# ft2232hq.net
KiCad netlist of a schematic drawn in Altium Designer
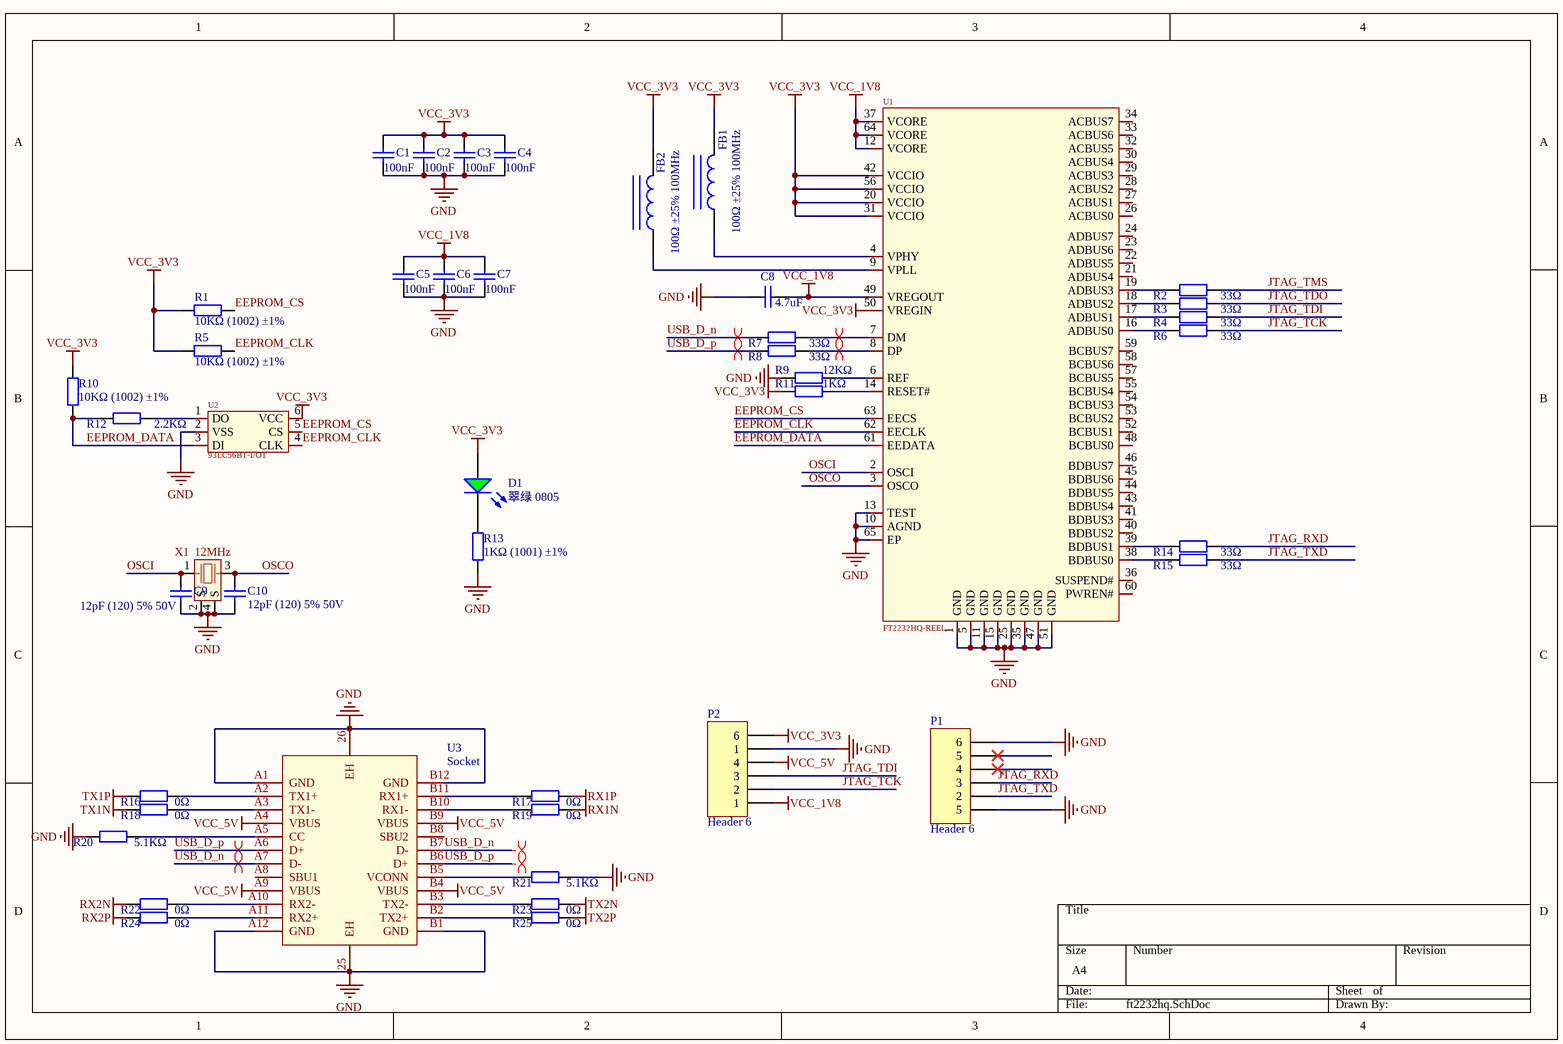
[diagram p0: ft2232hq.SchDoc]

(export (version "E")
  (design (tool "Eeschema 10.0.6"))
  (components
    (comp (ref "C1")
      (value "100nF")
      (footprint "0805_C")
      (description "贴片电容")
      (libsource (lib "Miscellaneous Devices LC") (part "0805 100nF(104) 10% 50V"))
    )
    (comp (ref "C2")
      (value "100nF")
      (footprint "0805_C")
      (description "贴片电容")
      (libsource (lib "Miscellaneous Devices LC") (part "0805 100nF(104) 10% 50V"))
    )
    (comp (ref "C3")
      (value "100nF")
      (footprint "0805_C")
      (description "贴片电容")
      (libsource (lib "Miscellaneous Devices LC") (part "0805 100nF(104) 10% 50V"))
    )
    (comp (ref "C4")
      (value "100nF")
      (footprint "0805_C")
      (description "贴片电容")
      (libsource (lib "Miscellaneous Devices LC") (part "0805 100nF(104) 10% 50V"))
    )
    (comp (ref "C5")
      (value "100nF")
      (footprint "0805_C")
      (description "贴片电容")
      (libsource (lib "Miscellaneous Devices LC") (part "0805 100nF(104) 10% 50V"))
    )
    (comp (ref "C6")
      (value "100nF")
      (footprint "0805_C")
      (description "贴片电容")
      (libsource (lib "Miscellaneous Devices LC") (part "0805 100nF(104) 10% 50V"))
    )
    (comp (ref "C7")
      (value "100nF")
      (footprint "0805_C")
      (description "贴片电容")
      (libsource (lib "Miscellaneous Devices LC") (part "0805 100nF(104) 10% 50V"))
    )
    (comp (ref "C8")
      (value "4.7uF")
      (footprint "0805_C")
      (description "贴片电容")
      (libsource (lib "Miscellaneous Devices LC") (part "0805 4.7uF (475) 10% 25V"))
    )
    (comp (ref "C9")
      (value "12pF (120) 5% 50V")
      (footprint "0805_C")
      (description "贴片电容")
      (libsource (lib "Miscellaneous Devices LC") (part "0805 12pF (120) 5% 50V"))
    )
    (comp (ref "C10")
      (value "12pF (120) 5% 50V")
      (footprint "0805_C")
      (description "贴片电容")
      (libsource (lib "Miscellaneous Devices LC") (part "0805 12pF (120) 5% 50V"))
    )
    (comp (ref "D1")
      (value "翠绿 0805")
      (footprint "0805_LED_S1")
      (description "发光二极管")
      (libsource (lib "Miscellaneous Devices LC") (part "0805 翠绿"))
    )
    (comp (ref "FB1")
      (value "100Ω ±25% 100MHz")
      (footprint "0805_L")
      (description "贴片磁珠")
      (libsource (lib "Miscellaneous Devices LC") (part "0805 100Ω 25% 100MHz"))
    )
    (comp (ref "FB2")
      (value "100Ω ±25% 100MHz")
      (footprint "0805_L")
      (description "贴片磁珠")
      (libsource (lib "Miscellaneous Devices LC") (part "0805 100Ω 25% 100MHz"))
    )
    (comp (ref "P1")
      (value "Header 6")
      (footprint "HDR1X6")
      (description "Header, 6-Pin")
      (fields (field (name "PUBLISHER") "Altium Limited"))
      (libsource (lib "") (part "Header 6_1"))
    )
    (comp (ref "P2")
      (value "Header 6")
      (footprint "HDR1X6")
      (description "Header, 6-Pin")
      (fields (field (name "PUBLISHER") "Altium Limited"))
      (libsource (lib "Miscellaneous Connectors") (part "Header 6"))
    )
    (comp (ref "R1")
      (value "10KΩ (1002) ±1%")
      (footprint "0805_R")
      (description "贴片电阻")
      (libsource (lib "") (part "0805 10KΩ (1002) 1%_1"))
    )
    (comp (ref "R2")
      (value "33Ω")
      (footprint "0805_R")
      (description "贴片电阻")
      (libsource (lib "Miscellaneous Devices LC") (part "0805 33Ω (33R0) 1%"))
    )
    (comp (ref "R3")
      (value "33Ω")
      (footprint "0805_R")
      (description "贴片电阻")
      (libsource (lib "Miscellaneous Devices LC") (part "0805 33Ω (33R0) 1%"))
    )
    (comp (ref "R4")
      (value "33Ω")
      (footprint "0805_R")
      (description "贴片电阻")
      (libsource (lib "Miscellaneous Devices LC") (part "0805 33Ω (33R0) 1%"))
    )
    (comp (ref "R5")
      (value "10KΩ (1002) ±1%")
      (footprint "0805_R")
      (description "贴片电阻")
      (libsource (lib "") (part "0805 10KΩ (1002) 1%_1"))
    )
    (comp (ref "R6")
      (value "33Ω")
      (footprint "0805_R")
      (description "贴片电阻")
      (libsource (lib "Miscellaneous Devices LC") (part "0805 33Ω (33R0) 1%"))
    )
    (comp (ref "R7")
      (value "33Ω")
      (footprint "0805_R")
      (description "贴片电阻")
      (libsource (lib "Miscellaneous Devices LC") (part "0805 33Ω (33R0) 1%"))
    )
    (comp (ref "R8")
      (value "33Ω")
      (footprint "0805_R")
      (description "贴片电阻")
      (libsource (lib "Miscellaneous Devices LC") (part "0805 33Ω (33R0) 1%"))
    )
    (comp (ref "R9")
      (value "12KΩ")
      (footprint "0805_R")
      (description "贴片电阻")
      (libsource (lib "Miscellaneous Devices LC") (part "0805 12KΩ (1202) 1%"))
    )
    (comp (ref "R10")
      (value "10KΩ (1002) ±1%")
      (footprint "0805_R")
      (description "贴片电阻")
      (libsource (lib "Miscellaneous Devices LC") (part "0805 10KΩ (1002) 1%"))
    )
    (comp (ref "R11")
      (value "1KΩ")
      (footprint "0805_R")
      (description "贴片电阻")
      (libsource (lib "Miscellaneous Devices LC") (part "0805 1KΩ (1001) 1%"))
    )
    (comp (ref "R12")
      (value "2.2KΩ")
      (footprint "0805_R")
      (description "贴片电阻")
      (libsource (lib "Miscellaneous Devices LC") (part "0805 2.2KΩ (2201) 1%"))
    )
    (comp (ref "R13")
      (value "1KΩ (1001) ±1%")
      (footprint "0805_R")
      (description "贴片电阻")
      (libsource (lib "") (part "0805 1KΩ (1001) 1%_1"))
    )
    (comp (ref "R14")
      (value "33Ω")
      (footprint "0805_R")
      (description "贴片电阻")
      (libsource (lib "Miscellaneous Devices LC") (part "0805 33Ω (33R0) 1%"))
    )
    (comp (ref "R15")
      (value "33Ω")
      (footprint "0805_R")
      (description "贴片电阻")
      (libsource (lib "Miscellaneous Devices LC") (part "0805 33Ω (33R0) 1%"))
    )
    (comp (ref "R16")
      (value "0Ω")
      (footprint "0402_R")
      (description "贴片电阻")
      (libsource (lib "Miscellaneous Devices LC") (part "0402 0Ω (0R0) 1%"))
    )
    (comp (ref "R17")
      (value "0Ω")
      (footprint "0402_R")
      (description "贴片电阻")
      (libsource (lib "Miscellaneous Devices LC") (part "0402 0Ω (0R0) 1%"))
    )
    (comp (ref "R18")
      (value "0Ω")
      (footprint "0402_R")
      (description "贴片电阻")
      (libsource (lib "Miscellaneous Devices LC") (part "0402 0Ω (0R0) 1%"))
    )
    (comp (ref "R19")
      (value "0Ω")
      (footprint "0402_R")
      (description "贴片电阻")
      (libsource (lib "Miscellaneous Devices LC") (part "0402 0Ω (0R0) 1%"))
    )
    (comp (ref "R20")
      (value "5.1KΩ")
      (footprint "0805_R")
      (description "贴片电阻")
      (libsource (lib "Miscellaneous Devices LC") (part "0805 5.1KΩ (5101) 1%"))
    )
    (comp (ref "R21")
      (value "5.1KΩ")
      (footprint "0805_R")
      (description "贴片电阻")
      (libsource (lib "Miscellaneous Devices LC") (part "0805 5.1KΩ (5101) 1%"))
    )
    (comp (ref "R22")
      (value "0Ω")
      (footprint "0402_R")
      (description "贴片电阻")
      (libsource (lib "Miscellaneous Devices LC") (part "0402 0Ω (0R0) 1%"))
    )
    (comp (ref "R23")
      (value "0Ω")
      (footprint "0402_R")
      (description "贴片电阻")
      (libsource (lib "Miscellaneous Devices LC") (part "0402 0Ω (0R0) 1%"))
    )
    (comp (ref "R24")
      (value "0Ω")
      (footprint "0402_R")
      (description "贴片电阻")
      (libsource (lib "Miscellaneous Devices LC") (part "0402 0Ω (0R0) 1%"))
    )
    (comp (ref "R25")
      (value "0Ω")
      (footprint "0402_R")
      (description "贴片电阻")
      (libsource (lib "Miscellaneous Devices LC") (part "0402 0Ω (0R0) 1%"))
    )
    (comp (ref "U1")
      (value "FT2232HQ-REEL")
      (footprint "QFN-64_L9.0-W9.0-P0.50-TL-EP4.3")
      (fields (field (name "MANUFACTURER") "FTDI(飞特帝亚)"))
      (libsource (lib "五向开关") (part "FT2232HQ-REEL"))
    )
    (comp (ref "U2")
      (value "93LC56BT-I/OT")
      (footprint "SOT-23-6_L2.9-W1.6-P0.95-LS2.8-BR")
      (fields (field (name "MANUFACTURER") "MICROCHIP(美国微芯)"))
      (libsource (lib "五向开关") (part "93LC56BT-I/OT"))
    )
    (comp (ref "U3")
      (value "Socket")
      (footprint "USB Type C 贴片 24P")
      (libsource (lib "五向开关") (part "USB type C 沉板公头"))
    )
    (comp (ref "X1")
      (value "12MHz")
      (footprint "3225")
      (description "4脚贴片无源晶体")
      (fields (field (name "MANUFACTURER") "YJX(雅晶鑫)") (field (name "MANUFACTURER PART") "TAXM8M4RDBCCT2T"))
      (libsource (lib "五向开关") (part "四脚无源晶体"))
    )
  )
  (nets
    (net (code "1") (name "/EEPROM_CLK") (class "Default")
      (node (ref "R5") (pin "1") (pinfunction "1_1") (pintype "passive"))
      (node (ref "U1") (pin "62") (pinfunction "EECLK_62") (pintype "passive"))
      (node (ref "U2") (pin "4") (pinfunction "CLK_4") (pintype "passive"))
    )
    (net (code "2") (name "/EEPROM_CS") (class "Default")
      (node (ref "R1") (pin "1") (pinfunction "1_1") (pintype "passive"))
      (node (ref "U1") (pin "63") (pinfunction "EECS_63") (pintype "passive"))
      (node (ref "U2") (pin "5") (pinfunction "CS_5") (pintype "passive"))
    )
    (net (code "3") (name "/EEPROM_DATA") (class "Default")
      (node (ref "R10") (pin "1") (pinfunction "1_1") (pintype "passive"))
      (node (ref "R12") (pin "1") (pinfunction "1_1") (pintype "passive"))
      (node (ref "U1") (pin "61") (pinfunction "EEDATA_61") (pintype "passive"))
      (node (ref "U2") (pin "3") (pinfunction "DI_3") (pintype "passive"))
    )
    (net (code "4") (name "/JTAG_RXD") (class "Default")
      (node (ref "P1") (pin "3") (pinfunction "3_3") (pintype "passive"))
      (node (ref "R14") (pin "2") (pinfunction "2_2") (pintype "passive"))
    )
    (net (code "5") (name "/JTAG_TCK") (class "Default")
      (node (ref "P2") (pin "2") (pinfunction "2_2") (pintype "passive"))
      (node (ref "R6") (pin "2") (pinfunction "2_2") (pintype "passive"))
    )
    (net (code "6") (name "/JTAG_TDI") (class "Default")
      (node (ref "P2") (pin "3") (pinfunction "3_3") (pintype "passive"))
      (node (ref "R4") (pin "2") (pinfunction "2_2") (pintype "passive"))
    )
    (net (code "7") (name "/JTAG_TDO") (class "Default")
      (node (ref "R3") (pin "2") (pinfunction "2_2") (pintype "passive"))
    )
    (net (code "8") (name "/JTAG_TMS") (class "Default")
      (node (ref "R2") (pin "2") (pinfunction "2_2") (pintype "passive"))
    )
    (net (code "9") (name "/JTAG_TXD") (class "Default")
      (node (ref "P1") (pin "2") (pinfunction "2_2") (pintype "passive"))
      (node (ref "R15") (pin "2") (pinfunction "2_2") (pintype "passive"))
    )
    (net (code "10") (name "/OSCI") (class "Default")
      (node (ref "C9") (pin "2") (pinfunction "2_2") (pintype "passive"))
      (node (ref "U1") (pin "2") (pinfunction "OSCI_2") (pintype "passive"))
      (node (ref "X1") (pin "1") (pintype "passive"))
    )
    (net (code "11") (name "/OSCO") (class "Default")
      (node (ref "C10") (pin "2") (pinfunction "2_2") (pintype "passive"))
      (node (ref "U1") (pin "3") (pinfunction "OSCO_3") (pintype "passive"))
      (node (ref "X1") (pin "3") (pintype "passive"))
    )
    (net (code "12") (name "/USB_D_n") (class "Default")
      (node (ref "R7") (pin "1") (pinfunction "1_1") (pintype "passive"))
      (node (ref "U3") (pin "A7") (pinfunction "D-_A7") (pintype "passive"))
      (node (ref "U3") (pin "B7") (pinfunction "D-_B7") (pintype "passive"))
    )
    (net (code "13") (name "/USB_D_p") (class "Default")
      (node (ref "R8") (pin "1") (pinfunction "1_1") (pintype "passive"))
      (node (ref "U3") (pin "A6") (pinfunction "D+_A6") (pintype "passive"))
      (node (ref "U3") (pin "B6") (pinfunction "D+_B6") (pintype "passive"))
    )
    (net (code "14") (name "GND") (class "Default")
      (node (ref "C1") (pin "1") (pinfunction "1_1") (pintype "passive"))
      (node (ref "C10") (pin "1") (pinfunction "1_1") (pintype "passive"))
      (node (ref "C2") (pin "1") (pinfunction "1_1") (pintype "passive"))
      (node (ref "C3") (pin "1") (pinfunction "1_1") (pintype "passive"))
      (node (ref "C4") (pin "1") (pinfunction "1_1") (pintype "passive"))
      (node (ref "C5") (pin "1") (pinfunction "1_1") (pintype "passive"))
      (node (ref "C6") (pin "1") (pinfunction "1_1") (pintype "passive"))
      (node (ref "C7") (pin "1") (pinfunction "1_1") (pintype "passive"))
      (node (ref "C8") (pin "1") (pinfunction "1_1") (pintype "passive"))
      (node (ref "C9") (pin "1") (pinfunction "1_1") (pintype "passive"))
      (node (ref "P1") (pin "5") (pinfunction "5_5") (pintype "passive"))
      (node (ref "P1") (pin "6") (pinfunction "6_6") (pintype "passive"))
      (node (ref "P2") (pin "1") (pinfunction "1_1") (pintype "passive"))
      (node (ref "R13") (pin "1") (pinfunction "1_1") (pintype "passive"))
      (node (ref "R20") (pin "1") (pinfunction "1_1") (pintype "passive"))
      (node (ref "R21") (pin "2") (pinfunction "2_2") (pintype "passive"))
      (node (ref "R9") (pin "1") (pinfunction "1_1") (pintype "passive"))
      (node (ref "U1") (pin "1") (pinfunction "GND_1") (pintype "passive"))
      (node (ref "U1") (pin "10") (pinfunction "AGND_10") (pintype "passive"))
      (node (ref "U1") (pin "11") (pinfunction "GND_11") (pintype "passive"))
      (node (ref "U1") (pin "13") (pinfunction "TEST_13") (pintype "passive"))
      (node (ref "U1") (pin "15") (pinfunction "GND_15") (pintype "passive"))
      (node (ref "U1") (pin "25") (pinfunction "GND_25") (pintype "passive"))
      (node (ref "U1") (pin "35") (pinfunction "GND_35") (pintype "passive"))
      (node (ref "U1") (pin "47") (pinfunction "GND_47") (pintype "passive"))
      (node (ref "U1") (pin "5") (pinfunction "GND_5") (pintype "passive"))
      (node (ref "U1") (pin "51") (pinfunction "GND_51") (pintype "passive"))
      (node (ref "U1") (pin "65") (pinfunction "EP_65") (pintype "passive"))
      (node (ref "U2") (pin "2") (pinfunction "VSS_2") (pintype "passive"))
      (node (ref "U3") (pin "25") (pinfunction "EH_25") (pintype "passive"))
      (node (ref "U3") (pin "26") (pinfunction "EH_26") (pintype "passive"))
      (node (ref "U3") (pin "A1") (pinfunction "GND_A1") (pintype "passive"))
      (node (ref "U3") (pin "A12") (pinfunction "GND_A12") (pintype "passive"))
      (node (ref "U3") (pin "B1") (pinfunction "GND_B1") (pintype "passive"))
      (node (ref "U3") (pin "B12") (pinfunction "GND_B12") (pintype "passive"))
      (node (ref "X1") (pin "2") (pinfunction "S_2") (pintype "passive"))
      (node (ref "X1") (pin "4") (pinfunction "S_4") (pintype "passive"))
    )
    (net (code "15") (name "Net-(D1-PadK)") (class "Default")
      (node (ref "D1") (pin "K") (pinfunction "K_K") (pintype "passive"))
      (node (ref "R13") (pin "2") (pinfunction "2_2") (pintype "passive"))
    )
    (net (code "16") (name "Net-(U1-ADBUS0)") (class "Default")
      (node (ref "R6") (pin "1") (pinfunction "1_1") (pintype "passive"))
      (node (ref "U1") (pin "16") (pinfunction "ADBUS0_16") (pintype "passive"))
    )
    (net (code "17") (name "Net-(U1-ADBUS1)") (class "Default")
      (node (ref "R4") (pin "1") (pinfunction "1_1") (pintype "passive"))
      (node (ref "U1") (pin "17") (pinfunction "ADBUS1_17") (pintype "passive"))
    )
    (net (code "18") (name "Net-(U1-ADBUS2)") (class "Default")
      (node (ref "R3") (pin "1") (pinfunction "1_1") (pintype "passive"))
      (node (ref "U1") (pin "18") (pinfunction "ADBUS2_18") (pintype "passive"))
    )
    (net (code "19") (name "Net-(U1-ADBUS3)") (class "Default")
      (node (ref "R2") (pin "1") (pinfunction "1_1") (pintype "passive"))
      (node (ref "U1") (pin "19") (pinfunction "ADBUS3_19") (pintype "passive"))
    )
    (net (code "20") (name "Net-(U1-BDBUS0)") (class "Default")
      (node (ref "R15") (pin "1") (pinfunction "1_1") (pintype "passive"))
      (node (ref "U1") (pin "38") (pinfunction "BDBUS0_38") (pintype "passive"))
    )
    (net (code "21") (name "Net-(U1-BDBUS1)") (class "Default")
      (node (ref "R14") (pin "1") (pinfunction "1_1") (pintype "passive"))
      (node (ref "U1") (pin "39") (pinfunction "BDBUS1_39") (pintype "passive"))
    )
    (net (code "22") (name "Net-(U1-DM)") (class "Default")
      (node (ref "R7") (pin "2") (pinfunction "2_2") (pintype "passive"))
      (node (ref "U1") (pin "7") (pinfunction "DM_7") (pintype "passive"))
    )
    (net (code "23") (name "Net-(U1-DP)") (class "Default")
      (node (ref "R8") (pin "2") (pinfunction "2_2") (pintype "passive"))
      (node (ref "U1") (pin "8") (pinfunction "DP_8") (pintype "passive"))
    )
    (net (code "24") (name "Net-(U1-REF)") (class "Default")
      (node (ref "R9") (pin "2") (pinfunction "2_2") (pintype "passive"))
      (node (ref "U1") (pin "6") (pinfunction "REF_6") (pintype "passive"))
    )
    (net (code "25") (name "Net-(U1-RESET#)") (class "Default")
      (node (ref "R11") (pin "2") (pinfunction "2_2") (pintype "passive"))
      (node (ref "U1") (pin "14") (pinfunction "RESET#_14") (pintype "passive"))
    )
    (net (code "26") (name "Net-(U1-VPHY)") (class "Default")
      (node (ref "FB1") (pin "1") (pinfunction "1_1") (pintype "passive"))
      (node (ref "U1") (pin "4") (pinfunction "VPHY_4") (pintype "passive"))
    )
    (net (code "27") (name "Net-(U1-VPLL)") (class "Default")
      (node (ref "FB2") (pin "1") (pinfunction "1_1") (pintype "passive"))
      (node (ref "U1") (pin "9") (pinfunction "VPLL_9") (pintype "passive"))
    )
    (net (code "28") (name "Net-(U2-DO)") (class "Default")
      (node (ref "R12") (pin "2") (pinfunction "2_2") (pintype "passive"))
      (node (ref "U2") (pin "1") (pinfunction "DO_1") (pintype "passive"))
    )
    (net (code "29") (name "Net-(U3-CC)") (class "Default")
      (node (ref "R20") (pin "2") (pinfunction "2_2") (pintype "passive"))
      (node (ref "U3") (pin "A5") (pinfunction "CC_A5") (pintype "passive"))
    )
    (net (code "30") (name "Net-(U3-RX1+)") (class "Default")
      (node (ref "R17") (pin "1") (pinfunction "1_1") (pintype "passive"))
      (node (ref "U3") (pin "B11") (pinfunction "RX1+_B11") (pintype "passive"))
    )
    (net (code "31") (name "Net-(U3-RX1-)") (class "Default")
      (node (ref "R19") (pin "1") (pinfunction "1_1") (pintype "passive"))
      (node (ref "U3") (pin "B10") (pinfunction "RX1-_B10") (pintype "passive"))
    )
    (net (code "32") (name "Net-(U3-RX2+)") (class "Default")
      (node (ref "R24") (pin "2") (pinfunction "2_2") (pintype "passive"))
      (node (ref "U3") (pin "A11") (pinfunction "RX2+_A11") (pintype "passive"))
    )
    (net (code "33") (name "Net-(U3-RX2-)") (class "Default")
      (node (ref "R22") (pin "2") (pinfunction "2_2") (pintype "passive"))
      (node (ref "U3") (pin "A10") (pinfunction "RX2-_A10") (pintype "passive"))
    )
    (net (code "34") (name "Net-(U3-TX1+)") (class "Default")
      (node (ref "R16") (pin "2") (pinfunction "2_2") (pintype "passive"))
      (node (ref "U3") (pin "A2") (pinfunction "TX1+_A2") (pintype "passive"))
    )
    (net (code "35") (name "Net-(U3-TX1-)") (class "Default")
      (node (ref "R18") (pin "2") (pinfunction "2_2") (pintype "passive"))
      (node (ref "U3") (pin "A3") (pinfunction "TX1-_A3") (pintype "passive"))
    )
    (net (code "36") (name "Net-(U3-TX2+)") (class "Default")
      (node (ref "R25") (pin "1") (pinfunction "1_1") (pintype "passive"))
      (node (ref "U3") (pin "B2") (pinfunction "TX2+_B2") (pintype "passive"))
    )
    (net (code "37") (name "Net-(U3-TX2-)") (class "Default")
      (node (ref "R23") (pin "1") (pinfunction "1_1") (pintype "passive"))
      (node (ref "U3") (pin "B3") (pinfunction "TX2-_B3") (pintype "passive"))
    )
    (net (code "38") (name "Net-(U3-VCONN)") (class "Default")
      (node (ref "R21") (pin "1") (pinfunction "1_1") (pintype "passive"))
      (node (ref "U3") (pin "B5") (pinfunction "VCONN_B5") (pintype "passive"))
    )
    (net (code "39") (name "RX1N") (class "Default")
      (node (ref "R19") (pin "2") (pinfunction "2_2") (pintype "passive"))
    )
    (net (code "40") (name "RX1P") (class "Default")
      (node (ref "R17") (pin "2") (pinfunction "2_2") (pintype "passive"))
    )
    (net (code "41") (name "RX2N") (class "Default")
      (node (ref "R22") (pin "1") (pinfunction "1_1") (pintype "passive"))
    )
    (net (code "42") (name "RX2P") (class "Default")
      (node (ref "R24") (pin "1") (pinfunction "1_1") (pintype "passive"))
    )
    (net (code "43") (name "TX1N") (class "Default")
      (node (ref "R18") (pin "1") (pinfunction "1_1") (pintype "passive"))
    )
    (net (code "44") (name "TX1P") (class "Default")
      (node (ref "R16") (pin "1") (pinfunction "1_1") (pintype "passive"))
    )
    (net (code "45") (name "TX2N") (class "Default")
      (node (ref "R23") (pin "2") (pinfunction "2_2") (pintype "passive"))
    )
    (net (code "46") (name "TX2P") (class "Default")
      (node (ref "R25") (pin "2") (pinfunction "2_2") (pintype "passive"))
    )
    (net (code "47") (name "VCC_1V8") (class "Default")
      (node (ref "C5") (pin "2") (pinfunction "2_2") (pintype "passive"))
      (node (ref "C6") (pin "2") (pinfunction "2_2") (pintype "passive"))
      (node (ref "C7") (pin "2") (pinfunction "2_2") (pintype "passive"))
      (node (ref "C8") (pin "2") (pinfunction "2_2") (pintype "passive"))
      (node (ref "P2") (pin "1") (pinfunction "1_1") (pintype "passive"))
      (node (ref "U1") (pin "12") (pinfunction "VCORE_12") (pintype "passive"))
      (node (ref "U1") (pin "37") (pinfunction "VCORE_37") (pintype "passive"))
      (node (ref "U1") (pin "49") (pinfunction "VREGOUT_49") (pintype "passive"))
      (node (ref "U1") (pin "64") (pinfunction "VCORE_64") (pintype "passive"))
    )
    (net (code "48") (name "VCC_3V3") (class "Default")
      (node (ref "C1") (pin "2") (pinfunction "2_2") (pintype "passive"))
      (node (ref "C2") (pin "2") (pinfunction "2_2") (pintype "passive"))
      (node (ref "C3") (pin "2") (pinfunction "2_2") (pintype "passive"))
      (node (ref "C4") (pin "2") (pinfunction "2_2") (pintype "passive"))
      (node (ref "D1") (pin "A") (pinfunction "A_A") (pintype "passive"))
      (node (ref "FB1") (pin "2") (pinfunction "2_2") (pintype "passive"))
      (node (ref "FB2") (pin "2") (pinfunction "2_2") (pintype "passive"))
      (node (ref "P2") (pin "6") (pinfunction "6_6") (pintype "passive"))
      (node (ref "R1") (pin "2") (pinfunction "2_2") (pintype "passive"))
      (node (ref "R10") (pin "2") (pinfunction "2_2") (pintype "passive"))
      (node (ref "R11") (pin "1") (pinfunction "1_1") (pintype "passive"))
      (node (ref "R5") (pin "2") (pinfunction "2_2") (pintype "passive"))
      (node (ref "U1") (pin "20") (pinfunction "VCCIO_20") (pintype "passive"))
      (node (ref "U1") (pin "31") (pinfunction "VCCIO_31") (pintype "passive"))
      (node (ref "U1") (pin "42") (pinfunction "VCCIO_42") (pintype "passive"))
      (node (ref "U1") (pin "50") (pinfunction "VREGIN_50") (pintype "passive"))
      (node (ref "U1") (pin "56") (pinfunction "VCCIO_56") (pintype "passive"))
      (node (ref "U2") (pin "6") (pinfunction "VCC_6") (pintype "passive"))
    )
    (net (code "49") (name "VCC_5V") (class "Default")
      (node (ref "P2") (pin "4") (pinfunction "4_4") (pintype "passive"))
      (node (ref "U3") (pin "A4") (pinfunction "VBUS_A4") (pintype "passive"))
      (node (ref "U3") (pin "A9") (pinfunction "VBUS_A9") (pintype "passive"))
      (node (ref "U3") (pin "B4") (pinfunction "VBUS_B4") (pintype "passive"))
      (node (ref "U3") (pin "B9") (pinfunction "VBUS_B9") (pintype "passive"))
    )
    (net (code "50") (name "unconnected-(P1-Pad4)") (class "Default")
      (node (ref "P1") (pin "4") (pinfunction "4_4") (pintype "passive+no_connect"))
    )
    (net (code "51") (name "unconnected-(P1-Pad5)") (class "Default")
      (node (ref "P1") (pin "5") (pinfunction "5_5") (pintype "passive+no_connect"))
    )
    (net (code "52") (name "unconnected-(U1-ACBUS0-Pad26)") (class "Default")
      (node (ref "U1") (pin "26") (pinfunction "ACBUS0_26") (pintype "passive"))
    )
    (net (code "53") (name "unconnected-(U1-ACBUS1-Pad27)") (class "Default")
      (node (ref "U1") (pin "27") (pinfunction "ACBUS1_27") (pintype "passive"))
    )
    (net (code "54") (name "unconnected-(U1-ACBUS2-Pad28)") (class "Default")
      (node (ref "U1") (pin "28") (pinfunction "ACBUS2_28") (pintype "passive"))
    )
    (net (code "55") (name "unconnected-(U1-ACBUS3-Pad29)") (class "Default")
      (node (ref "U1") (pin "29") (pinfunction "ACBUS3_29") (pintype "passive"))
    )
    (net (code "56") (name "unconnected-(U1-ACBUS4-Pad30)") (class "Default")
      (node (ref "U1") (pin "30") (pinfunction "ACBUS4_30") (pintype "passive"))
    )
    (net (code "57") (name "unconnected-(U1-ACBUS5-Pad32)") (class "Default")
      (node (ref "U1") (pin "32") (pinfunction "ACBUS5_32") (pintype "passive"))
    )
    (net (code "58") (name "unconnected-(U1-ACBUS6-Pad33)") (class "Default")
      (node (ref "U1") (pin "33") (pinfunction "ACBUS6_33") (pintype "passive"))
    )
    (net (code "59") (name "unconnected-(U1-ACBUS7-Pad34)") (class "Default")
      (node (ref "U1") (pin "34") (pinfunction "ACBUS7_34") (pintype "passive"))
    )
    (net (code "60") (name "unconnected-(U1-ADBUS4-Pad21)") (class "Default")
      (node (ref "U1") (pin "21") (pinfunction "ADBUS4_21") (pintype "passive"))
    )
    (net (code "61") (name "unconnected-(U1-ADBUS5-Pad22)") (class "Default")
      (node (ref "U1") (pin "22") (pinfunction "ADBUS5_22") (pintype "passive"))
    )
    (net (code "62") (name "unconnected-(U1-ADBUS6-Pad23)") (class "Default")
      (node (ref "U1") (pin "23") (pinfunction "ADBUS6_23") (pintype "passive"))
    )
    (net (code "63") (name "unconnected-(U1-ADBUS7-Pad24)") (class "Default")
      (node (ref "U1") (pin "24") (pinfunction "ADBUS7_24") (pintype "passive"))
    )
    (net (code "64") (name "unconnected-(U1-BCBUS0-Pad48)") (class "Default")
      (node (ref "U1") (pin "48") (pinfunction "BCBUS0_48") (pintype "passive"))
    )
    (net (code "65") (name "unconnected-(U1-BCBUS1-Pad52)") (class "Default")
      (node (ref "U1") (pin "52") (pinfunction "BCBUS1_52") (pintype "passive"))
    )
    (net (code "66") (name "unconnected-(U1-BCBUS2-Pad53)") (class "Default")
      (node (ref "U1") (pin "53") (pinfunction "BCBUS2_53") (pintype "passive"))
    )
    (net (code "67") (name "unconnected-(U1-BCBUS3-Pad54)") (class "Default")
      (node (ref "U1") (pin "54") (pinfunction "BCBUS3_54") (pintype "passive"))
    )
    (net (code "68") (name "unconnected-(U1-BCBUS4-Pad55)") (class "Default")
      (node (ref "U1") (pin "55") (pinfunction "BCBUS4_55") (pintype "passive"))
    )
    (net (code "69") (name "unconnected-(U1-BCBUS5-Pad57)") (class "Default")
      (node (ref "U1") (pin "57") (pinfunction "BCBUS5_57") (pintype "passive"))
    )
    (net (code "70") (name "unconnected-(U1-BCBUS6-Pad58)") (class "Default")
      (node (ref "U1") (pin "58") (pinfunction "BCBUS6_58") (pintype "passive"))
    )
    (net (code "71") (name "unconnected-(U1-BCBUS7-Pad59)") (class "Default")
      (node (ref "U1") (pin "59") (pinfunction "BCBUS7_59") (pintype "passive"))
    )
    (net (code "72") (name "unconnected-(U1-BDBUS2-Pad40)") (class "Default")
      (node (ref "U1") (pin "40") (pinfunction "BDBUS2_40") (pintype "passive"))
    )
    (net (code "73") (name "unconnected-(U1-BDBUS3-Pad41)") (class "Default")
      (node (ref "U1") (pin "41") (pinfunction "BDBUS3_41") (pintype "passive"))
    )
    (net (code "74") (name "unconnected-(U1-BDBUS4-Pad43)") (class "Default")
      (node (ref "U1") (pin "43") (pinfunction "BDBUS4_43") (pintype "passive"))
    )
    (net (code "75") (name "unconnected-(U1-BDBUS5-Pad44)") (class "Default")
      (node (ref "U1") (pin "44") (pinfunction "BDBUS5_44") (pintype "passive"))
    )
    (net (code "76") (name "unconnected-(U1-BDBUS6-Pad45)") (class "Default")
      (node (ref "U1") (pin "45") (pinfunction "BDBUS6_45") (pintype "passive"))
    )
    (net (code "77") (name "unconnected-(U1-BDBUS7-Pad46)") (class "Default")
      (node (ref "U1") (pin "46") (pinfunction "BDBUS7_46") (pintype "passive"))
    )
    (net (code "78") (name "unconnected-(U1-PWREN#-Pad60)") (class "Default")
      (node (ref "U1") (pin "60") (pinfunction "PWREN#_60") (pintype "passive"))
    )
    (net (code "79") (name "unconnected-(U1-SUSPEND#-Pad36)") (class "Default")
      (node (ref "U1") (pin "36") (pinfunction "SUSPEND#_36") (pintype "passive"))
    )
    (net (code "80") (name "unconnected-(U3-SBU1-PadA8)") (class "Default")
      (node (ref "U3") (pin "A8") (pinfunction "SBU1_A8") (pintype "passive"))
    )
    (net (code "81") (name "unconnected-(U3-SBU2-PadB8)") (class "Default")
      (node (ref "U3") (pin "B8") (pinfunction "SBU2_B8") (pintype "passive"))
    )
  )
)
